# Power_regulation.net
KiCad netlist of a schematic drawn in Altium Designer
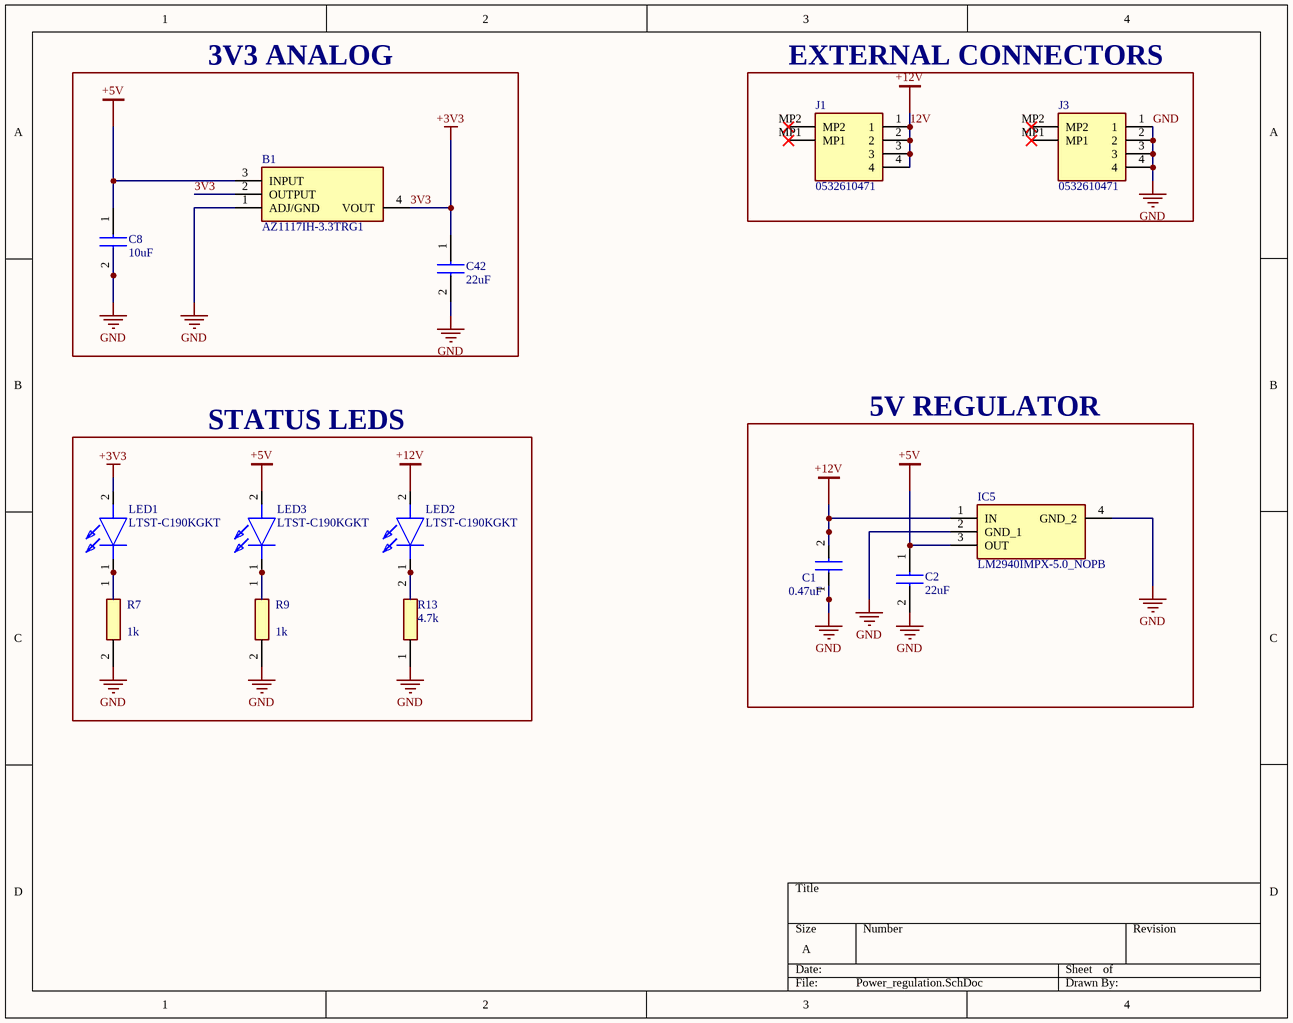
[diagram p0: Power_regulation.SchDoc]

(export (version "E")
  (design (tool "Eeschema 10.0.6"))
  (components
    (comp (ref "B1")
      (value "AZ1117IH-3.3TRG1")
      (footprint "SOT230P700X180-4N")
      (description "LDO Voltage Regulators LDO BJT HiCurr 1.35A 10Hz to 10KHz")
      (fields (field (name "MOUSER PART NUMBER") "621-AZ1117IH-3.3TRG1"))
      (libsource (lib "Americas- Calgary to Space- Calgary University") (part "AZ1117IH-3.3TRG1"))
    )
    (comp (ref "C1")
      (value "0.47uF")
      (footprint "SamacSys:CAPC1608X90N")
      (description "GRM188R61H474KA12D")
      (fields (field (name "MOUSER PART NUMBER") "81-GRM188R61H474KA2D"))
      (libsource (lib "*") (part "GRM188R61H474KA12D"))
    )
    (comp (ref "C2")
      (value "22uF")
      (footprint "SamacSys:CAPC1608X100N")
      (description "CC0603MRX5R6BB226")
      (fields (field (name "MOUSER PART NUMBER") "603-CC603MRX5R6BB226"))
      (libsource (lib "*") (part "CC0603MRX5R6BB226"))
    )
    (comp (ref "C8")
      (value "10uF")
      (footprint "SamacSys:GRM15x")
      (description "GRM155R61A106ME11D")
      (fields (field (name "MOUSER PART NUMBER") "81-GRM155R61A106ME1D"))
      (libsource (lib "*") (part "GRM155R61A106ME11D"))
    )
    (comp (ref "C42")
      (value "22uF")
      (footprint "SamacSys:CAPC1608X100N")
      (description "CC0603MRX5R6BB226")
      (fields (field (name "MOUSER PART NUMBER") "603-CC603MRX5R6BB226"))
      (libsource (lib "*") (part "CC0603MRX5R6BB226"))
    )
    (comp (ref "IC5")
      (value "LM2940IMPX-5.0_NOPB")
      (footprint "SamacSys:SOT230P700X180-4N")
      (description "Integrated Circuit")
      (fields
        (field (name "MANUFACTURER_PART_NUMBER") "LM2940IMPX-5.0/NOPB")
        (field (name "MOUSER PART NUMBER") "926-LM2940IMPX50NOPB")
      )
      (libsource (lib "*") (part "LM2940IMPX-5.0_NOPB"))
    )
    (comp (ref "J1")
      (value "0532610471")
      (footprint "SamacSys:0532610471")
      (description "Connector")
      (libsource (lib "*") (part "0532610471"))
    )
    (comp (ref "J3")
      (value "0532610471")
      (footprint "SamacSys:0532610471")
      (description "Connector")
      (libsource (lib "*") (part "0532610471"))
    )
    (comp (ref "LED1")
      (value "LTST-C190KGKT")
      (footprint "SamacSys:LEDC1608X80N")
      (description "LED")
      (fields (field (name "MOUSER PART NUMBER") "859-LTST-C190KGKT"))
      (libsource (lib "*") (part "LTST-C190KGKT"))
    )
    (comp (ref "LED2")
      (value "LTST-C190KGKT")
      (footprint "SamacSys:LEDC1608X80N")
      (description "LED")
      (fields (field (name "MOUSER PART NUMBER") "859-LTST-C190KGKT"))
      (libsource (lib "*") (part "LTST-C190KGKT"))
    )
    (comp (ref "LED3")
      (value "LTST-C190KGKT")
      (footprint "SamacSys:LEDC1608X80N")
      (description "LED")
      (fields (field (name "MOUSER PART NUMBER") "859-LTST-C190KGKT"))
      (libsource (lib "*") (part "LTST-C190KGKT"))
    )
    (comp (ref "R7")
      (value "1k")
      (footprint "SamacSys:RESC1608X55N")
      (description "RC0603FR-131KL")
      (fields (field (name "MOUSER PART NUMBER") "603-RC0603FR-131KL"))
      (libsource (lib "*") (part "RC0603FR-131KL"))
    )
    (comp (ref "R9")
      (value "1k")
      (footprint "SamacSys:RESC1608X55N")
      (description "RC0603FR-131KL")
      (fields (field (name "MOUSER PART NUMBER") "603-RC0603FR-131KL"))
      (libsource (lib "*") (part "RC0603FR-131KL"))
    )
    (comp (ref "R13")
      (value "4.7k")
      (footprint "SamacSys:RESC1608X55N")
      (description "AC0603FR-074K7L")
      (fields (field (name "MOUSER PART NUMBER") "603-AC0603FR-074K7L"))
      (libsource (lib "*") (part "AC0603FR-074K7L"))
    )
  )
  (nets
    (net (code "1") (name "+3V3") (class "Default")
      (node (ref "B1") (pin "2") (pinfunction "OUTPUT_2") (pintype "passive"))
      (node (ref "B1") (pin "4") (pinfunction "VOUT_4") (pintype "passive"))
      (node (ref "C42") (pin "1") (pinfunction "1_1") (pintype "passive"))
      (node (ref "LED1") (pin "2") (pinfunction "A_2") (pintype "passive"))
    )
    (net (code "2") (name "+5V") (class "Default")
      (node (ref "B1") (pin "3") (pinfunction "INPUT_3") (pintype "passive"))
      (node (ref "C2") (pin "1") (pinfunction "1_1") (pintype "passive"))
      (node (ref "C8") (pin "1") (pinfunction "1_1") (pintype "passive"))
      (node (ref "IC5") (pin "3") (pinfunction "OUT_3") (pintype "passive"))
      (node (ref "LED3") (pin "2") (pinfunction "A_2") (pintype "passive"))
    )
    (net (code "3") (name "+12V") (class "Default")
      (node (ref "C1") (pin "2") (pinfunction "2_2") (pintype "passive"))
      (node (ref "IC5") (pin "1") (pinfunction "IN_1") (pintype "passive"))
      (node (ref "J1") (pin "1") (pinfunction "1_1") (pintype "passive"))
      (node (ref "J1") (pin "2") (pinfunction "2_2") (pintype "passive"))
      (node (ref "J1") (pin "3") (pinfunction "3_3") (pintype "passive"))
      (node (ref "J1") (pin "4") (pinfunction "4_4") (pintype "passive"))
      (node (ref "LED2") (pin "2") (pinfunction "A_2") (pintype "passive"))
    )
    (net (code "4") (name "GND") (class "Default")
      (node (ref "B1") (pin "1") (pinfunction "ADJ/GND_1") (pintype "passive"))
      (node (ref "C1") (pin "1") (pinfunction "1_1") (pintype "passive"))
      (node (ref "C2") (pin "2") (pinfunction "2_2") (pintype "passive"))
      (node (ref "C42") (pin "2") (pinfunction "2_2") (pintype "passive"))
      (node (ref "C8") (pin "2") (pinfunction "2_2") (pintype "passive"))
      (node (ref "IC5") (pin "2") (pinfunction "GND_1_2") (pintype "passive"))
      (node (ref "IC5") (pin "4") (pinfunction "GND_2_4") (pintype "passive"))
      (node (ref "J3") (pin "1") (pinfunction "1_1") (pintype "passive"))
      (node (ref "J3") (pin "2") (pinfunction "2_2") (pintype "passive"))
      (node (ref "J3") (pin "3") (pinfunction "3_3") (pintype "passive"))
      (node (ref "J3") (pin "4") (pinfunction "4_4") (pintype "passive"))
      (node (ref "R13") (pin "1") (pinfunction "1_1") (pintype "passive"))
      (node (ref "R7") (pin "2") (pinfunction "2_2") (pintype "passive"))
      (node (ref "R9") (pin "2") (pinfunction "2_2") (pintype "passive"))
    )
    (net (code "5") (name "Net-(LED1-K)") (class "Default")
      (node (ref "LED1") (pin "1") (pinfunction "K_1") (pintype "passive"))
      (node (ref "R7") (pin "1") (pinfunction "1_1") (pintype "passive"))
    )
    (net (code "6") (name "Net-(LED2-K)") (class "Default")
      (node (ref "LED2") (pin "1") (pinfunction "K_1") (pintype "passive"))
      (node (ref "R13") (pin "2") (pinfunction "2_2") (pintype "passive"))
    )
    (net (code "7") (name "Net-(LED3-K)") (class "Default")
      (node (ref "LED3") (pin "1") (pinfunction "K_1") (pintype "passive"))
      (node (ref "R9") (pin "1") (pinfunction "1_1") (pintype "passive"))
    )
    (net (code "8") (name "unconnected-(J1-PadMP1)") (class "Default")
      (node (ref "J1") (pin "MP1") (pinfunction "MP1_MP1") (pintype "passive+no_connect"))
    )
    (net (code "9") (name "unconnected-(J1-PadMP2)") (class "Default")
      (node (ref "J1") (pin "MP2") (pinfunction "MP2_MP2") (pintype "passive+no_connect"))
    )
    (net (code "10") (name "unconnected-(J3-PadMP1)") (class "Default")
      (node (ref "J3") (pin "MP1") (pinfunction "MP1_MP1") (pintype "passive+no_connect"))
    )
    (net (code "11") (name "unconnected-(J3-PadMP2)") (class "Default")
      (node (ref "J3") (pin "MP2") (pinfunction "MP2_MP2") (pintype "passive+no_connect"))
    )
  )
)
